# breeze_power.net
KiCad netlist of a schematic drawn in Altium Designer
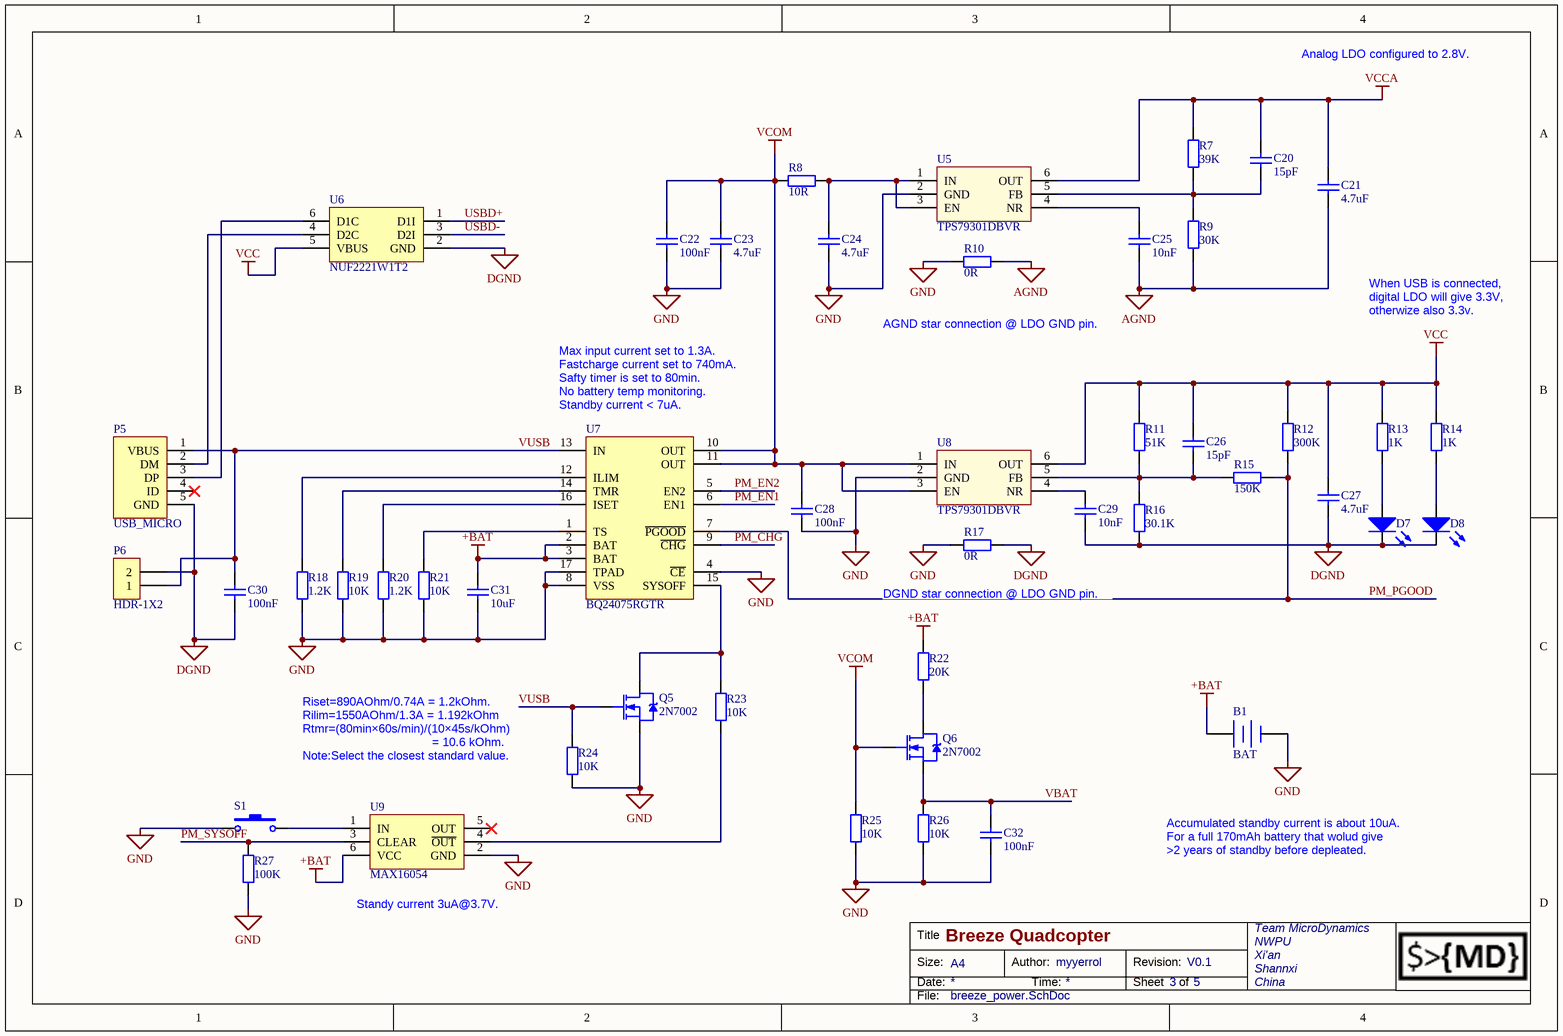
[diagram p0: breeze_power.SchDoc]

(export (version "E")
  (design (tool "Eeschema 10.0.6"))
  (components
    (comp (ref "B1")
      (value "BAT")
      (footprint "HDR-1X2")
      (description "Battery")
      (libsource (lib "breeze_design_library") (part "BAT"))
    )
    (comp (ref "C20")
      (value "15pF")
      (footprint "SMD-0603")
      (description "Capacitor")
      (fields (field (name "Comment") "CAP-0603"))
      (libsource (lib "breeze_design_library") (part "CAP-0603"))
    )
    (comp (ref "C21")
      (value "4.7uF")
      (footprint "SMD-0603")
      (description "Capacitor")
      (fields (field (name "Comment") "CAP-0603"))
      (libsource (lib "breeze_design_library") (part "CAP-0603"))
    )
    (comp (ref "C22")
      (value "100nF")
      (footprint "SMD-0603")
      (description "Capacitor")
      (fields (field (name "Comment") "CAP-0603"))
      (libsource (lib "breeze_design_library") (part "CAP-0603"))
    )
    (comp (ref "C23")
      (value "4.7uF")
      (footprint "SMD-0603")
      (description "Capacitor")
      (fields (field (name "Comment") "CAP-0603"))
      (libsource (lib "breeze_design_library") (part "CAP-0603"))
    )
    (comp (ref "C24")
      (value "4.7uF")
      (footprint "SMD-0603")
      (description "Capacitor")
      (fields (field (name "Comment") "CAP-0603"))
      (libsource (lib "breeze_design_library") (part "CAP-0603"))
    )
    (comp (ref "C25")
      (value "10nF")
      (footprint "SMD-0603")
      (description "Capacitor")
      (fields (field (name "Comment") "CAP-0603"))
      (libsource (lib "breeze_design_library") (part "CAP-0603"))
    )
    (comp (ref "C26")
      (value "15pF")
      (footprint "SMD-0603")
      (description "Capacitor")
      (fields (field (name "Comment") "CAP-0603"))
      (libsource (lib "breeze_design_library") (part "CAP-0603"))
    )
    (comp (ref "C27")
      (value "4.7uF")
      (footprint "SMD-0603")
      (description "Capacitor")
      (fields (field (name "Comment") "CAP-0603"))
      (libsource (lib "breeze_design_library") (part "CAP-0603"))
    )
    (comp (ref "C28")
      (value "100nF")
      (footprint "SMD-0603")
      (description "Capacitor")
      (fields (field (name "Comment") "CAP-0603"))
      (libsource (lib "breeze_design_library") (part "CAP-0603"))
    )
    (comp (ref "C29")
      (value "10nF")
      (footprint "SMD-0603")
      (description "Capacitor")
      (fields (field (name "Comment") "CAP-0603"))
      (libsource (lib "breeze_design_library") (part "CAP-0603"))
    )
    (comp (ref "C30")
      (value "100nF")
      (footprint "SMD-0603")
      (description "Capacitor")
      (fields (field (name "Comment") "CAP-0603"))
      (libsource (lib "breeze_design_library") (part "CAP-0603"))
    )
    (comp (ref "C31")
      (value "10uF")
      (footprint "SMD-0603")
      (description "Capacitor")
      (fields (field (name "Comment") "CAP-0603"))
      (libsource (lib "breeze_design_library") (part "CAP-0603"))
    )
    (comp (ref "C32")
      (value "100nF")
      (footprint "SMD-0603")
      (description "Capacitor")
      (fields (field (name "Comment") "CAP-0603"))
      (libsource (lib "breeze_design_library") (part "CAP-0603"))
    )
    (comp (ref "D7")
      (value "LED-0603")
      (footprint "SMD-0603")
      (description "LED")
      (libsource (lib "breeze_design_library") (part "LED-0603"))
    )
    (comp (ref "D8")
      (value "LED-0603")
      (footprint "SMD-0603")
      (description "LED")
      (libsource (lib "breeze_design_library") (part "LED-0603"))
    )
    (comp (ref "P5")
      (value "USB_MICRO")
      (footprint "USB_MICRO")
      (description "Micro USB")
      (libsource (lib "breeze_design_library") (part "USB_MICRO"))
    )
    (comp (ref "P6")
      (value "HDR-1X2")
      (footprint "HDR-1X2")
      (description "Header 1X2")
      (libsource (lib "breeze_design_library") (part "HDR-1X2"))
    )
    (comp (ref "Q5")
      (value "2N7002")
      (footprint "SOT-23")
      (description "N-Channel Enhancement Mode Field Effect Transistor")
      (libsource (lib "breeze_design_library") (part "2N7002"))
    )
    (comp (ref "Q6")
      (value "2N7002")
      (footprint "SOT-23")
      (description "N-Channel Enhancement Mode Field Effect Transistor")
      (libsource (lib "breeze_design_library") (part "2N7002"))
    )
    (comp (ref "R7")
      (value "39K")
      (footprint "SMD-0603")
      (description "Resistor")
      (fields (field (name "Comment") "RES-0603"))
      (libsource (lib "breeze_design_library") (part "RES-0603"))
    )
    (comp (ref "R8")
      (value "10R")
      (footprint "SMD-0603")
      (description "Resistor")
      (fields (field (name "Comment") "RES-0603"))
      (libsource (lib "") (part "RES-0603_1"))
    )
    (comp (ref "R9")
      (value "30K")
      (footprint "SMD-0603")
      (description "Resistor")
      (fields (field (name "Comment") "RES-0603"))
      (libsource (lib "breeze_design_library") (part "RES-0603"))
    )
    (comp (ref "R10")
      (value "0R")
      (footprint "SMD-0603")
      (description "Resistor")
      (fields (field (name "Comment") "RES-0603"))
      (libsource (lib "") (part "RES-0603_1"))
    )
    (comp (ref "R11")
      (value "51K")
      (footprint "SMD-0603")
      (description "Resistor")
      (fields (field (name "Comment") "RES-0603"))
      (libsource (lib "breeze_design_library") (part "RES-0603"))
    )
    (comp (ref "R12")
      (value "300K")
      (footprint "SMD-0603")
      (description "Resistor")
      (fields (field (name "Comment") "RES-0603"))
      (libsource (lib "breeze_design_library") (part "RES-0603"))
    )
    (comp (ref "R13")
      (value "1K")
      (footprint "SMD-0603")
      (description "Resistor")
      (fields (field (name "Comment") "RES-0603"))
      (libsource (lib "breeze_design_library") (part "RES-0603"))
    )
    (comp (ref "R14")
      (value "1K")
      (footprint "SMD-0603")
      (description "Resistor")
      (fields (field (name "Comment") "RES-0603"))
      (libsource (lib "breeze_design_library") (part "RES-0603"))
    )
    (comp (ref "R15")
      (value "150K")
      (footprint "SMD-0603")
      (description "Resistor")
      (fields (field (name "Comment") "RES-0603"))
      (libsource (lib "") (part "RES-0603_1"))
    )
    (comp (ref "R16")
      (value "30.1K")
      (footprint "SMD-0603")
      (description "Resistor")
      (fields (field (name "Comment") "RES-0603"))
      (libsource (lib "breeze_design_library") (part "RES-0603"))
    )
    (comp (ref "R17")
      (value "0R")
      (footprint "SMD-0603")
      (description "Resistor")
      (fields (field (name "Comment") "RES-0603"))
      (libsource (lib "") (part "RES-0603_1"))
    )
    (comp (ref "R18")
      (value "1.2K")
      (footprint "SMD-0603")
      (description "Resistor")
      (fields (field (name "Comment") "RES-0603"))
      (libsource (lib "breeze_design_library") (part "RES-0603"))
    )
    (comp (ref "R19")
      (value "10K")
      (footprint "SMD-0603")
      (description "Resistor")
      (fields (field (name "Comment") "RES-0603"))
      (libsource (lib "breeze_design_library") (part "RES-0603"))
    )
    (comp (ref "R20")
      (value "1.2K")
      (footprint "SMD-0603")
      (description "Resistor")
      (fields (field (name "Comment") "RES-0603"))
      (libsource (lib "breeze_design_library") (part "RES-0603"))
    )
    (comp (ref "R21")
      (value "10K")
      (footprint "SMD-0603")
      (description "Resistor")
      (fields (field (name "Comment") "RES-0603"))
      (libsource (lib "breeze_design_library") (part "RES-0603"))
    )
    (comp (ref "R22")
      (value "20K")
      (footprint "SMD-0603")
      (description "Resistor")
      (fields (field (name "Comment") "RES-0603"))
      (libsource (lib "breeze_design_library") (part "RES-0603"))
    )
    (comp (ref "R23")
      (value "10K")
      (footprint "SMD-0603")
      (description "Resistor")
      (fields (field (name "Comment") "RES-0603"))
      (libsource (lib "breeze_design_library") (part "RES-0603"))
    )
    (comp (ref "R24")
      (value "10K")
      (footprint "SMD-0603")
      (description "Resistor")
      (fields (field (name "Comment") "RES-0603"))
      (libsource (lib "breeze_design_library") (part "RES-0603"))
    )
    (comp (ref "R25")
      (value "10K")
      (footprint "SMD-0603")
      (description "Resistor")
      (fields (field (name "Comment") "RES-0603"))
      (libsource (lib "breeze_design_library") (part "RES-0603"))
    )
    (comp (ref "R26")
      (value "10K")
      (footprint "SMD-0603")
      (description "Resistor")
      (fields (field (name "Comment") "RES-0603"))
      (libsource (lib "breeze_design_library") (part "RES-0603"))
    )
    (comp (ref "R27")
      (value "100K")
      (footprint "SMD-0603")
      (description "Resistor")
      (fields (field (name "Comment") "RES-0603"))
      (libsource (lib "breeze_design_library") (part "RES-0603"))
    )
    (comp (ref "S1")
      (value "SKRELGE010")
      (footprint "SKRELGE010")
      (description "Switch")
      (libsource (lib "breeze_design_library") (part "SKRELGE010"))
    )
    (comp (ref "U5")
      (value "TPS79301DBVR")
      (footprint "SOT-23-6")
      (description "200-mA RF Low-Dropout Regulator")
      (libsource (lib "breeze_design_library") (part "TPS79301DBVR"))
    )
    (comp (ref "U6")
      (value "NUF2221W1T2")
      (footprint "SOT-363")
      (description "USB Upstream Terminator  with ESD Protection")
      (libsource (lib "breeze_design_library") (part "NUF2221W1T2"))
    )
    (comp (ref "U7")
      (value "BQ24075RGTR")
      (footprint "VQFN-16")
      (description "1.5-A USB-Friendly Li-Ion Battery Charger and Power-Path Management IC")
      (libsource (lib "breeze_design_library") (part "BQ24075RGTR"))
    )
    (comp (ref "U8")
      (value "TPS79301DBVR")
      (footprint "SOT-23-6")
      (description "200-mA RF Low-Dropout Regulator")
      (libsource (lib "breeze_design_library") (part "TPS79301DBVR"))
    )
    (comp (ref "U9")
      (value "MAX16054")
      (footprint "SOT-23-6")
      (description "On/Off Controller with Debounce and ±15kV ESD Protection")
      (libsource (lib "breeze_design_library") (part "MAX16054"))
    )
  )
  (nets
    (net (code "1") (name "+BAT") (class "Default")
      (node (ref "B1") (pin "1") (pinfunction "+_1") (pintype "passive"))
      (node (ref "C31") (pin "1") (pinfunction "1_1") (pintype "passive"))
      (node (ref "R22") (pin "1") (pinfunction "1_1") (pintype "passive"))
      (node (ref "U7") (pin "2") (pinfunction "BAT_2") (pintype "passive"))
      (node (ref "U7") (pin "3") (pinfunction "BAT_3") (pintype "passive"))
      (node (ref "U9") (pin "6") (pinfunction "VCC_6") (pintype "passive"))
    )
    (net (code "2") (name "/PM_CHG") (class "Default")
      (node (ref "U7") (pin "9") (pinfunction "~{CHG}_9") (pintype "passive"))
    )
    (net (code "3") (name "/PM_EN1") (class "Default")
      (node (ref "U7") (pin "6") (pinfunction "EN1_6") (pintype "passive"))
    )
    (net (code "4") (name "/PM_EN2") (class "Default")
      (node (ref "U7") (pin "5") (pinfunction "EN2_5") (pintype "passive"))
    )
    (net (code "5") (name "/PM_PGOOD") (class "Default")
      (node (ref "R12") (pin "2") (pinfunction "2_2") (pintype "passive"))
      (node (ref "R15") (pin "2") (pinfunction "2_2") (pintype "passive"))
      (node (ref "U7") (pin "7") (pinfunction "~{PGOOD}_7") (pintype "passive"))
    )
    (net (code "6") (name "/PM_SYSOFF") (class "Default")
      (node (ref "R27") (pin "1") (pinfunction "1_1") (pintype "passive"))
      (node (ref "U9") (pin "3") (pinfunction "CLEAR_3") (pintype "passive"))
    )
    (net (code "7") (name "/USBD+") (class "Default")
      (node (ref "U6") (pin "1") (pinfunction "D1I_1") (pintype "passive"))
    )
    (net (code "8") (name "/USBD-") (class "Default")
      (node (ref "U6") (pin "3") (pinfunction "D2I_3") (pintype "passive"))
    )
    (net (code "9") (name "/VBAT") (class "Default")
      (node (ref "C32") (pin "1") (pinfunction "1_1") (pintype "passive"))
      (node (ref "Q6") (pin "2") (pinfunction "S_2") (pintype "passive"))
      (node (ref "R26") (pin "1") (pinfunction "1_1") (pintype "passive"))
    )
    (net (code "10") (name "/VUSB") (class "Default")
      (node (ref "C30") (pin "1") (pinfunction "1_1") (pintype "passive"))
      (node (ref "P5") (pin "1") (pinfunction "VBUS_1") (pintype "passive"))
      (node (ref "P6") (pin "1") (pinfunction "1_1") (pintype "passive"))
      (node (ref "Q5") (pin "1") (pinfunction "G_1") (pintype "passive"))
      (node (ref "R24") (pin "1") (pinfunction "1_1") (pintype "passive"))
      (node (ref "U7") (pin "13") (pinfunction "IN_13") (pintype "passive"))
    )
    (net (code "11") (name "AGND") (class "Default")
      (node (ref "C21") (pin "2") (pinfunction "2_2") (pintype "passive"))
      (node (ref "C25") (pin "2") (pinfunction "2_2") (pintype "passive"))
      (node (ref "R10") (pin "2") (pinfunction "2_2") (pintype "passive"))
      (node (ref "R9") (pin "2") (pinfunction "2_2") (pintype "passive"))
    )
    (net (code "12") (name "DGND") (class "Default")
      (node (ref "C27") (pin "2") (pinfunction "2_2") (pintype "passive"))
      (node (ref "C29") (pin "2") (pinfunction "2_2") (pintype "passive"))
      (node (ref "C30") (pin "2") (pinfunction "2_2") (pintype "passive"))
      (node (ref "D7") (pin "2") (pinfunction "K_2") (pintype "passive"))
      (node (ref "D8") (pin "2") (pinfunction "K_2") (pintype "passive"))
      (node (ref "P5") (pin "5") (pinfunction "GND_5") (pintype "passive"))
      (node (ref "P6") (pin "2") (pinfunction "2_2") (pintype "passive"))
      (node (ref "R16") (pin "2") (pinfunction "2_2") (pintype "passive"))
      (node (ref "R17") (pin "2") (pinfunction "2_2") (pintype "passive"))
      (node (ref "U6") (pin "2") (pinfunction "GND_2") (pintype "passive"))
    )
    (net (code "13") (name "GND") (class "Default")
      (node (ref "B1") (pin "2") (pinfunction "-_2") (pintype "passive"))
      (node (ref "C22") (pin "2") (pinfunction "2_2") (pintype "passive"))
      (node (ref "C23") (pin "2") (pinfunction "2_2") (pintype "passive"))
      (node (ref "C24") (pin "2") (pinfunction "2_2") (pintype "passive"))
      (node (ref "C28") (pin "2") (pinfunction "2_2") (pintype "passive"))
      (node (ref "C31") (pin "2") (pinfunction "2_2") (pintype "passive"))
      (node (ref "C32") (pin "2") (pinfunction "2_2") (pintype "passive"))
      (node (ref "Q5") (pin "2") (pinfunction "S_2") (pintype "passive"))
      (node (ref "R10") (pin "1") (pinfunction "1_1") (pintype "passive"))
      (node (ref "R17") (pin "1") (pinfunction "1_1") (pintype "passive"))
      (node (ref "R18") (pin "2") (pinfunction "2_2") (pintype "passive"))
      (node (ref "R19") (pin "2") (pinfunction "2_2") (pintype "passive"))
      (node (ref "R20") (pin "2") (pinfunction "2_2") (pintype "passive"))
      (node (ref "R21") (pin "2") (pinfunction "2_2") (pintype "passive"))
      (node (ref "R24") (pin "2") (pinfunction "2_2") (pintype "passive"))
      (node (ref "R25") (pin "2") (pinfunction "2_2") (pintype "passive"))
      (node (ref "R26") (pin "2") (pinfunction "2_2") (pintype "passive"))
      (node (ref "R27") (pin "2") (pinfunction "2_2") (pintype "passive"))
      (node (ref "S1") (pin "1") (pinfunction "1_1") (pintype "passive"))
      (node (ref "U5") (pin "2") (pinfunction "GND_2") (pintype "power_in"))
      (node (ref "U7") (pin "17") (pinfunction "TPAD_17") (pintype "passive"))
      (node (ref "U7") (pin "4") (pinfunction "~{CE}_4") (pintype "passive"))
      (node (ref "U7") (pin "8") (pinfunction "VSS_8") (pintype "passive"))
      (node (ref "U8") (pin "2") (pinfunction "GND_2") (pintype "power_in"))
      (node (ref "U9") (pin "2") (pinfunction "GND_2") (pintype "passive"))
    )
    (net (code "14") (name "Net-(D7-A)") (class "Default")
      (node (ref "D7") (pin "1") (pinfunction "A_1") (pintype "passive"))
      (node (ref "R13") (pin "2") (pinfunction "2_2") (pintype "passive"))
    )
    (net (code "15") (name "Net-(D8-A)") (class "Default")
      (node (ref "D8") (pin "1") (pinfunction "A_1") (pintype "passive"))
      (node (ref "R14") (pin "2") (pinfunction "2_2") (pintype "passive"))
    )
    (net (code "16") (name "Net-(P5-DM)") (class "Default")
      (node (ref "P5") (pin "2") (pinfunction "DM_2") (pintype "passive"))
      (node (ref "U6") (pin "4") (pinfunction "D2C_4") (pintype "passive"))
    )
    (net (code "17") (name "Net-(P5-DP)") (class "Default")
      (node (ref "P5") (pin "3") (pinfunction "DP_3") (pintype "passive"))
      (node (ref "U6") (pin "6") (pinfunction "D1C_6") (pintype "passive"))
    )
    (net (code "18") (name "Net-(Q5-D)") (class "Default")
      (node (ref "Q5") (pin "3") (pinfunction "D_3") (pintype "passive"))
      (node (ref "R23") (pin "1") (pinfunction "1_1") (pintype "passive"))
      (node (ref "U7") (pin "15") (pinfunction "SYSOFF_15") (pintype "passive"))
    )
    (net (code "19") (name "Net-(Q6-D)") (class "Default")
      (node (ref "Q6") (pin "3") (pinfunction "D_3") (pintype "passive"))
      (node (ref "R22") (pin "2") (pinfunction "2_2") (pintype "passive"))
    )
    (net (code "20") (name "Net-(U5-EN)") (class "Default")
      (node (ref "C24") (pin "1") (pinfunction "1_1") (pintype "passive"))
      (node (ref "R8") (pin "2") (pinfunction "2_2") (pintype "passive"))
      (node (ref "U5") (pin "1") (pinfunction "IN_1") (pintype "passive"))
      (node (ref "U5") (pin "3") (pinfunction "EN_3") (pintype "passive"))
    )
    (net (code "21") (name "Net-(U5-FB)") (class "Default")
      (node (ref "C20") (pin "2") (pinfunction "2_2") (pintype "passive"))
      (node (ref "R7") (pin "2") (pinfunction "2_2") (pintype "passive"))
      (node (ref "R9") (pin "1") (pinfunction "1_1") (pintype "passive"))
      (node (ref "U5") (pin "5") (pinfunction "FB_5") (pintype "passive"))
    )
    (net (code "22") (name "Net-(U5-NR)") (class "Default")
      (node (ref "C25") (pin "1") (pinfunction "1_1") (pintype "passive"))
      (node (ref "U5") (pin "4") (pinfunction "NR_4") (pintype "passive"))
    )
    (net (code "23") (name "Net-(U7-ILIM)") (class "Default")
      (node (ref "R18") (pin "1") (pinfunction "1_1") (pintype "passive"))
      (node (ref "U7") (pin "12") (pinfunction "ILIM_12") (pintype "passive"))
    )
    (net (code "24") (name "Net-(U7-ISET)") (class "Default")
      (node (ref "R20") (pin "1") (pinfunction "1_1") (pintype "passive"))
      (node (ref "U7") (pin "16") (pinfunction "ISET_16") (pintype "passive"))
    )
    (net (code "25") (name "Net-(U7-TMR)") (class "Default")
      (node (ref "R19") (pin "1") (pinfunction "1_1") (pintype "passive"))
      (node (ref "U7") (pin "14") (pinfunction "TMR_14") (pintype "passive"))
    )
    (net (code "26") (name "Net-(U7-TS)") (class "Default")
      (node (ref "R21") (pin "1") (pinfunction "1_1") (pintype "passive"))
      (node (ref "U7") (pin "1") (pinfunction "TS_1") (pintype "passive"))
    )
    (net (code "27") (name "Net-(U8-FB)") (class "Default")
      (node (ref "C26") (pin "2") (pinfunction "2_2") (pintype "passive"))
      (node (ref "R11") (pin "2") (pinfunction "2_2") (pintype "passive"))
      (node (ref "R15") (pin "1") (pinfunction "1_1") (pintype "passive"))
      (node (ref "R16") (pin "1") (pinfunction "1_1") (pintype "passive"))
      (node (ref "U8") (pin "5") (pinfunction "FB_5") (pintype "passive"))
    )
    (net (code "28") (name "Net-(U8-NR)") (class "Default")
      (node (ref "C29") (pin "1") (pinfunction "1_1") (pintype "passive"))
      (node (ref "U8") (pin "4") (pinfunction "NR_4") (pintype "passive"))
    )
    (net (code "29") (name "Net-(U9-IN)") (class "Default")
      (node (ref "S1") (pin "2") (pinfunction "2_2") (pintype "passive"))
      (node (ref "U9") (pin "1") (pinfunction "IN_1") (pintype "passive"))
    )
    (net (code "30") (name "Net-(U9-~{OUT})") (class "Default")
      (node (ref "R23") (pin "2") (pinfunction "2_2") (pintype "passive"))
      (node (ref "U9") (pin "4") (pinfunction "~{OUT}_4") (pintype "passive"))
    )
    (net (code "31") (name "VCC") (class "Default")
      (node (ref "C26") (pin "1") (pinfunction "1_1") (pintype "passive"))
      (node (ref "C27") (pin "1") (pinfunction "1_1") (pintype "passive"))
      (node (ref "R11") (pin "1") (pinfunction "1_1") (pintype "passive"))
      (node (ref "R12") (pin "1") (pinfunction "1_1") (pintype "passive"))
      (node (ref "R13") (pin "1") (pinfunction "1_1") (pintype "passive"))
      (node (ref "R14") (pin "1") (pinfunction "1_1") (pintype "passive"))
      (node (ref "U6") (pin "5") (pinfunction "VBUS_5") (pintype "passive"))
      (node (ref "U8") (pin "6") (pinfunction "OUT_6") (pintype "passive"))
    )
    (net (code "32") (name "VCCA") (class "Default")
      (node (ref "C20") (pin "1") (pinfunction "1_1") (pintype "passive"))
      (node (ref "C21") (pin "1") (pinfunction "1_1") (pintype "passive"))
      (node (ref "R7") (pin "1") (pinfunction "1_1") (pintype "passive"))
      (node (ref "U5") (pin "6") (pinfunction "OUT_6") (pintype "passive"))
    )
    (net (code "33") (name "VCOM") (class "Default")
      (node (ref "C22") (pin "1") (pinfunction "1_1") (pintype "passive"))
      (node (ref "C23") (pin "1") (pinfunction "1_1") (pintype "passive"))
      (node (ref "C28") (pin "1") (pinfunction "1_1") (pintype "passive"))
      (node (ref "Q6") (pin "1") (pinfunction "G_1") (pintype "passive"))
      (node (ref "R25") (pin "1") (pinfunction "1_1") (pintype "passive"))
      (node (ref "R8") (pin "1") (pinfunction "1_1") (pintype "passive"))
      (node (ref "U7") (pin "10") (pinfunction "OUT_10") (pintype "passive"))
      (node (ref "U7") (pin "11") (pinfunction "OUT_11") (pintype "passive"))
      (node (ref "U8") (pin "1") (pinfunction "IN_1") (pintype "passive"))
      (node (ref "U8") (pin "3") (pinfunction "EN_3") (pintype "passive"))
    )
    (net (code "34") (name "unconnected-(P5-ID-Pad4)") (class "Default")
      (node (ref "P5") (pin "4") (pinfunction "ID_4") (pintype "passive+no_connect"))
    )
    (net (code "35") (name "unconnected-(U9-OUT-Pad5)") (class "Default")
      (node (ref "U9") (pin "5") (pinfunction "OUT_5") (pintype "passive+no_connect"))
    )
  )
)
